# ECG.net
KiCad netlist of a schematic drawn in Altium Designer
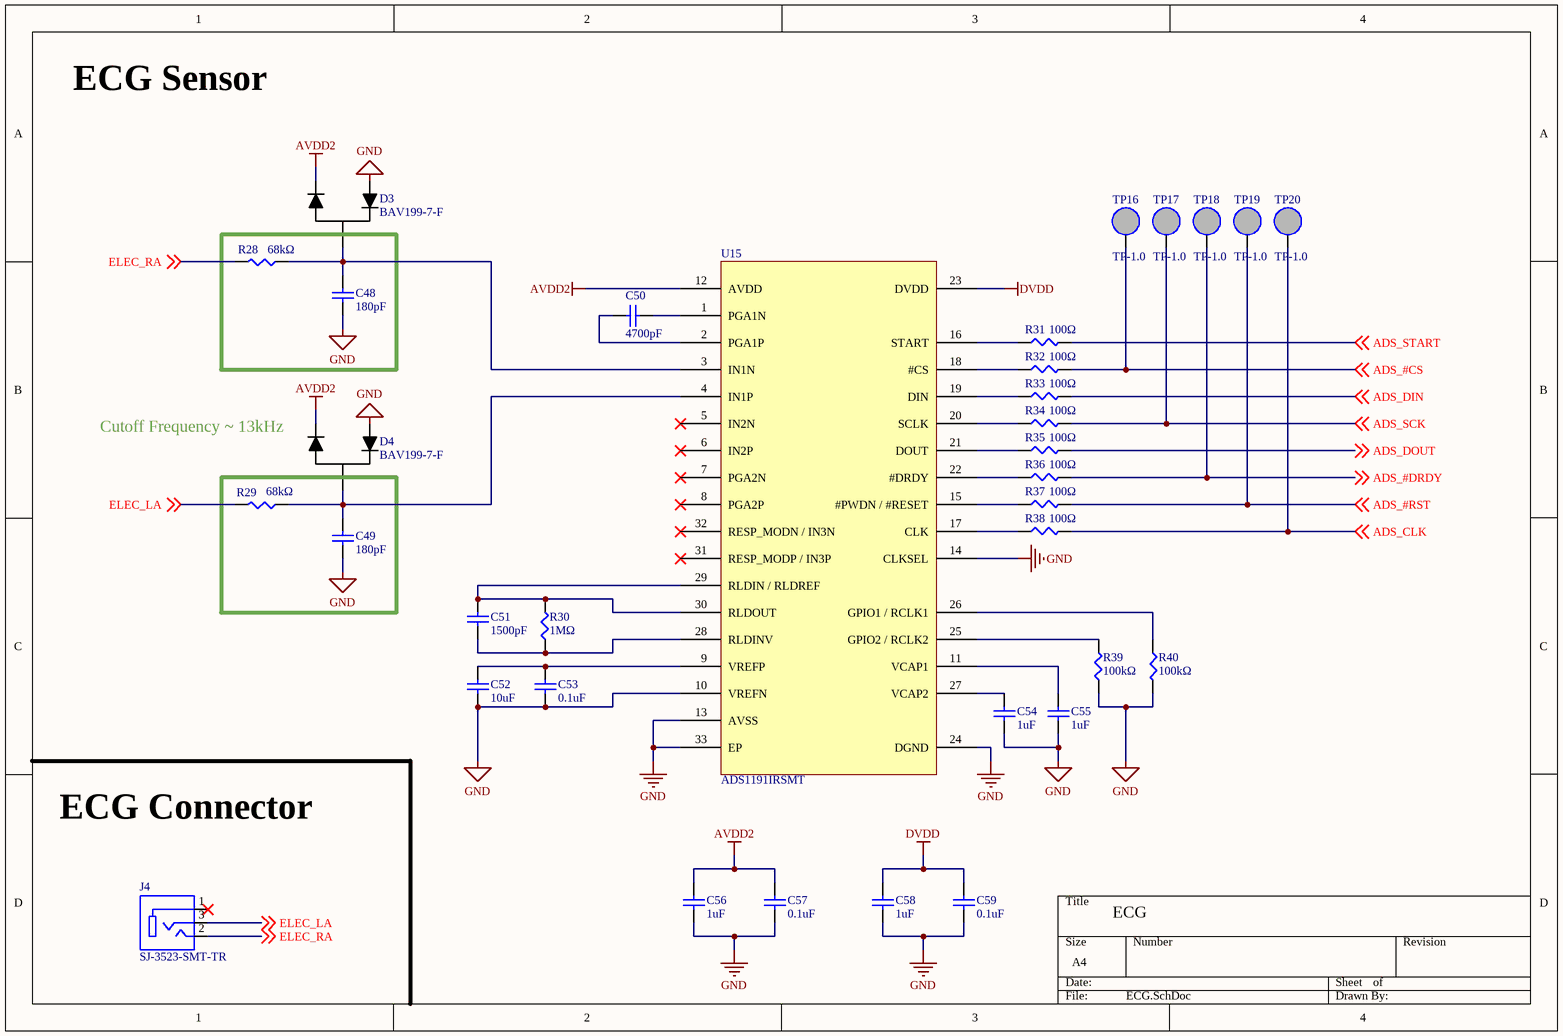
[diagram p0: ECG.SchDoc]

(export (version "E")
  (design (tool "Eeschema 10.0.6"))
  (components
    (comp (ref "C48")
      (value "180pF")
      (footprint "0402")
      (description "MLCC-0402")
      (libsource (lib "MLCC") (part "0402"))
    )
    (comp (ref "C49")
      (value "180pF")
      (footprint "0402")
      (description "MLCC-0402")
      (libsource (lib "MLCC") (part "0402"))
    )
    (comp (ref "C50")
      (value "4700pF")
      (footprint "0402")
      (description "MLCC-0402")
      (libsource (lib "MLCC") (part "0402"))
    )
    (comp (ref "C51")
      (value "1500pF")
      (footprint "0402")
      (description "MLCC-0402")
      (libsource (lib "MLCC") (part "0402"))
    )
    (comp (ref "C52")
      (value "10uF")
      (footprint "0603")
      (description "MLCC-0603")
      (libsource (lib "MLCC") (part "0603"))
    )
    (comp (ref "C53")
      (value "0.1uF")
      (footprint "0402")
      (description "MLCC-0402")
      (libsource (lib "MLCC") (part "0402"))
    )
    (comp (ref "C54")
      (value "1uF")
      (footprint "0402")
      (description "MLCC-0402")
      (libsource (lib "MLCC") (part "0402"))
    )
    (comp (ref "C55")
      (value "1uF")
      (footprint "0402")
      (description "MLCC-0402")
      (libsource (lib "MLCC") (part "0402"))
    )
    (comp (ref "C56")
      (value "1uF")
      (footprint "0402")
      (description "MLCC-0402")
      (libsource (lib "MLCC") (part "0402"))
    )
    (comp (ref "C57")
      (value "0.1uF")
      (footprint "0402")
      (description "MLCC-0402")
      (libsource (lib "MLCC") (part "0402"))
    )
    (comp (ref "C58")
      (value "1uF")
      (footprint "0402")
      (description "MLCC-0402")
      (libsource (lib "MLCC") (part "0402"))
    )
    (comp (ref "C59")
      (value "0.1uF")
      (footprint "0402")
      (description "MLCC-0402")
      (libsource (lib "MLCC") (part "0402"))
    )
    (comp (ref "D3")
      (value "BAV199-7-F")
      (footprint "SOT-23")
      (description "Dual Surface Mount Low Leakage Diode")
      (libsource (lib "BAV199") (part "BAV199-7-F"))
    )
    (comp (ref "D4")
      (value "BAV199-7-F")
      (footprint "SOT-23")
      (description "Dual Surface Mount Low Leakage Diode")
      (libsource (lib "BAV199") (part "BAV199-7-F"))
    )
    (comp (ref "J4")
      (value "SJ-3523-SMT-TR")
      (footprint "CUI_SJ-3523-SMT-TR")
      (description "3.5 mm, Stereo, Right Angle, Surface Mount _SMT_, Audio Jack Connector")
      (fields (field (name "MF") "CUI Devices"))
      (libsource (lib "SJ-3523-SMT-TR") (part "SJ-3523-SMT-TR"))
    )
    (comp (ref "R28")
      (value "68kΩ")
      (footprint "0402")
      (description "Resistor_SMD_0402")
      (fields (field (name "AUTHORBY") "yjlab"))
      (libsource (lib "Resistor") (part "0402"))
    )
    (comp (ref "R29")
      (value "68kΩ")
      (footprint "0402")
      (description "Resistor_SMD_0402")
      (fields (field (name "AUTHORBY") "yjlab"))
      (libsource (lib "Resistor") (part "0402"))
    )
    (comp (ref "R30")
      (value "1MΩ")
      (footprint "0402")
      (description "Resistor_SMD_0402")
      (fields (field (name "AUTHORBY") "yjlab"))
      (libsource (lib "Resistor") (part "0402"))
    )
    (comp (ref "R31")
      (value "100Ω")
      (footprint "0402")
      (description "Resistor_SMD_0402")
      (fields (field (name "AUTHORBY") "yjlab"))
      (libsource (lib "Resistor") (part "0402"))
    )
    (comp (ref "R32")
      (value "100Ω")
      (footprint "0402")
      (description "Resistor_SMD_0402")
      (fields (field (name "AUTHORBY") "yjlab"))
      (libsource (lib "Resistor") (part "0402"))
    )
    (comp (ref "R33")
      (value "100Ω")
      (footprint "0402")
      (description "Resistor_SMD_0402")
      (fields (field (name "AUTHORBY") "yjlab"))
      (libsource (lib "Resistor") (part "0402"))
    )
    (comp (ref "R34")
      (value "100Ω")
      (footprint "0402")
      (description "Resistor_SMD_0402")
      (fields (field (name "AUTHORBY") "yjlab"))
      (libsource (lib "Resistor") (part "0402"))
    )
    (comp (ref "R35")
      (value "100Ω")
      (footprint "0402")
      (description "Resistor_SMD_0402")
      (fields (field (name "AUTHORBY") "yjlab"))
      (libsource (lib "Resistor") (part "0402"))
    )
    (comp (ref "R36")
      (value "100Ω")
      (footprint "0402")
      (description "Resistor_SMD_0402")
      (fields (field (name "AUTHORBY") "yjlab"))
      (libsource (lib "Resistor") (part "0402"))
    )
    (comp (ref "R37")
      (value "100Ω")
      (footprint "0402")
      (description "Resistor_SMD_0402")
      (fields (field (name "AUTHORBY") "yjlab"))
      (libsource (lib "Resistor") (part "0402"))
    )
    (comp (ref "R38")
      (value "100Ω")
      (footprint "0402")
      (description "Resistor_SMD_0402")
      (fields (field (name "AUTHORBY") "yjlab"))
      (libsource (lib "Resistor") (part "0402"))
    )
    (comp (ref "R39")
      (value "100kΩ")
      (footprint "0402")
      (description "Resistor_SMD_0402")
      (fields (field (name "AUTHORBY") "yjlab"))
      (libsource (lib "Resistor") (part "0402"))
    )
    (comp (ref "R40")
      (value "100kΩ")
      (footprint "0402")
      (description "Resistor_SMD_0402")
      (fields (field (name "AUTHORBY") "yjlab"))
      (libsource (lib "Resistor") (part "0402"))
    )
    (comp (ref "TP16")
      (value "TP-1.0")
      (footprint "Testpoint")
      (libsource (lib "Testpoint") (part "Testpoint"))
    )
    (comp (ref "TP17")
      (value "TP-1.0")
      (footprint "Testpoint")
      (libsource (lib "Testpoint") (part "Testpoint"))
    )
    (comp (ref "TP18")
      (value "TP-1.0")
      (footprint "Testpoint")
      (libsource (lib "Testpoint") (part "Testpoint"))
    )
    (comp (ref "TP19")
      (value "TP-1.0")
      (footprint "Testpoint")
      (libsource (lib "Testpoint") (part "Testpoint"))
    )
    (comp (ref "TP20")
      (value "TP-1.0")
      (footprint "Testpoint")
      (libsource (lib "Testpoint") (part "Testpoint"))
    )
    (comp (ref "U15")
      (value "ADS1191IRSMT")
      (footprint "VQFN-32")
      (description "Biopotential Measurement ADC, 2 Channel, 16 Bit")
      (libsource (lib "ADS119x") (part "ADS1191IRSMT"))
    )
  )
  (nets
    (net (code "1") (name "ADS_#CS") (class "Default")
      (node (ref "R32") (pin "2") (pinfunction "2_2") (pintype "passive"))
      (node (ref "TP16") (pin "1") (pinfunction "1_1") (pintype "passive"))
    )
    (net (code "2") (name "ADS_#DRDY") (class "Default")
      (node (ref "R36") (pin "2") (pinfunction "2_2") (pintype "passive"))
      (node (ref "TP18") (pin "1") (pinfunction "1_1") (pintype "passive"))
    )
    (net (code "3") (name "ADS_#RST") (class "Default")
      (node (ref "R37") (pin "2") (pinfunction "2_2") (pintype "passive"))
      (node (ref "TP19") (pin "1") (pinfunction "1_1") (pintype "passive"))
    )
    (net (code "4") (name "ADS_CLK") (class "Default")
      (node (ref "R38") (pin "2") (pinfunction "2_2") (pintype "passive"))
      (node (ref "TP20") (pin "1") (pinfunction "1_1") (pintype "passive"))
    )
    (net (code "5") (name "ADS_DIN") (class "Default")
      (node (ref "R33") (pin "2") (pinfunction "2_2") (pintype "passive"))
    )
    (net (code "6") (name "ADS_DOUT") (class "Default")
      (node (ref "R35") (pin "2") (pinfunction "2_2") (pintype "passive"))
    )
    (net (code "7") (name "ADS_SCK") (class "Default")
      (node (ref "R34") (pin "2") (pinfunction "2_2") (pintype "passive"))
      (node (ref "TP17") (pin "1") (pinfunction "1_1") (pintype "passive"))
    )
    (net (code "8") (name "ADS_START") (class "Default")
      (node (ref "R31") (pin "2") (pinfunction "2_2") (pintype "passive"))
    )
    (net (code "9") (name "AVDD2") (class "Default")
      (node (ref "C56") (pin "2") (pinfunction "2_2") (pintype "passive"))
      (node (ref "C57") (pin "2") (pinfunction "2_2") (pintype "passive"))
      (node (ref "D3") (pin "3") (pinfunction "Cathode_3") (pintype "passive"))
      (node (ref "D4") (pin "3") (pinfunction "Cathode_3") (pintype "passive"))
      (node (ref "U15") (pin "12") (pinfunction "AVDD_12") (pintype "passive"))
    )
    (net (code "10") (name "DVDD") (class "Default")
      (node (ref "C58") (pin "2") (pinfunction "2_2") (pintype "passive"))
      (node (ref "C59") (pin "2") (pinfunction "2_2") (pintype "passive"))
      (node (ref "U15") (pin "23") (pinfunction "DVDD_23") (pintype "passive"))
    )
    (net (code "11") (name "ELEC_LA") (class "Default")
      (node (ref "J4") (pin "3") (pinfunction "3_3") (pintype "passive"))
      (node (ref "R29") (pin "2") (pinfunction "2_2") (pintype "passive"))
    )
    (net (code "12") (name "ELEC_RA") (class "Default")
      (node (ref "J4") (pin "2") (pinfunction "2_2") (pintype "passive"))
      (node (ref "R28") (pin "2") (pinfunction "2_2") (pintype "passive"))
    )
    (net (code "13") (name "GND") (class "Default")
      (node (ref "C48") (pin "1") (pinfunction "1_1") (pintype "passive"))
      (node (ref "C49") (pin "1") (pinfunction "1_1") (pintype "passive"))
      (node (ref "C52") (pin "1") (pinfunction "1_1") (pintype "passive"))
      (node (ref "C53") (pin "1") (pinfunction "1_1") (pintype "passive"))
      (node (ref "C54") (pin "2") (pinfunction "2_2") (pintype "passive"))
      (node (ref "C55") (pin "2") (pinfunction "2_2") (pintype "passive"))
      (node (ref "C56") (pin "1") (pinfunction "1_1") (pintype "passive"))
      (node (ref "C57") (pin "1") (pinfunction "1_1") (pintype "passive"))
      (node (ref "C58") (pin "1") (pinfunction "1_1") (pintype "passive"))
      (node (ref "C59") (pin "1") (pinfunction "1_1") (pintype "passive"))
      (node (ref "D3") (pin "2") (pinfunction "Anode_2") (pintype "passive"))
      (node (ref "D4") (pin "2") (pinfunction "Anode_2") (pintype "passive"))
      (node (ref "R39") (pin "1") (pinfunction "1_1") (pintype "passive"))
      (node (ref "R40") (pin "2") (pinfunction "2_2") (pintype "passive"))
      (node (ref "U15") (pin "10") (pinfunction "VREFN_10") (pintype "passive"))
      (node (ref "U15") (pin "13") (pinfunction "AVSS_13") (pintype "passive"))
      (node (ref "U15") (pin "14") (pinfunction "CLKSEL_14") (pintype "passive"))
      (node (ref "U15") (pin "24") (pinfunction "DGND_24") (pintype "passive"))
      (node (ref "U15") (pin "33") (pinfunction "EP_33") (pintype "passive"))
    )
    (net (code "14") (name "Net-(D3-Common)") (class "Default")
      (node (ref "C48") (pin "2") (pinfunction "2_2") (pintype "passive"))
      (node (ref "D3") (pin "1") (pinfunction "Common_1") (pintype "passive"))
      (node (ref "R28") (pin "1") (pinfunction "1_1") (pintype "passive"))
      (node (ref "U15") (pin "3") (pinfunction "IN1N_3") (pintype "passive"))
    )
    (net (code "15") (name "Net-(D4-Common)") (class "Default")
      (node (ref "C49") (pin "2") (pinfunction "2_2") (pintype "passive"))
      (node (ref "D4") (pin "1") (pinfunction "Common_1") (pintype "passive"))
      (node (ref "R29") (pin "1") (pinfunction "1_1") (pintype "passive"))
      (node (ref "U15") (pin "4") (pinfunction "IN1P_4") (pintype "passive"))
    )
    (net (code "16") (name "Net-(U15-#CS)") (class "Default")
      (node (ref "R32") (pin "1") (pinfunction "1_1") (pintype "passive"))
      (node (ref "U15") (pin "18") (pinfunction "#CS_18") (pintype "passive"))
    )
    (net (code "17") (name "Net-(U15-#DRDY)") (class "Default")
      (node (ref "R36") (pin "1") (pinfunction "1_1") (pintype "passive"))
      (node (ref "U15") (pin "22") (pinfunction "#DRDY_22") (pintype "passive"))
    )
    (net (code "18") (name "Net-(U15-#PWDN_{slash}_#RESET)") (class "Default")
      (node (ref "R37") (pin "1") (pinfunction "1_1") (pintype "passive"))
      (node (ref "U15") (pin "15") (pinfunction "#PWDN_/_#RESET_15") (pintype "passive"))
    )
    (net (code "19") (name "Net-(U15-CLK)") (class "Default")
      (node (ref "R38") (pin "1") (pinfunction "1_1") (pintype "passive"))
      (node (ref "U15") (pin "17") (pinfunction "CLK_17") (pintype "passive"))
    )
    (net (code "20") (name "Net-(U15-DIN)") (class "Default")
      (node (ref "R33") (pin "1") (pinfunction "1_1") (pintype "passive"))
      (node (ref "U15") (pin "19") (pinfunction "DIN_19") (pintype "passive"))
    )
    (net (code "21") (name "Net-(U15-DOUT)") (class "Default")
      (node (ref "R35") (pin "1") (pinfunction "1_1") (pintype "passive"))
      (node (ref "U15") (pin "21") (pinfunction "DOUT_21") (pintype "passive"))
    )
    (net (code "22") (name "Net-(U15-GPIO1_{slash}_RCLK1)") (class "Default")
      (node (ref "R40") (pin "1") (pinfunction "1_1") (pintype "passive"))
      (node (ref "U15") (pin "26") (pinfunction "GPIO1_/_RCLK1_26") (pintype "passive"))
    )
    (net (code "23") (name "Net-(U15-GPIO2_{slash}_RCLK2)") (class "Default")
      (node (ref "R39") (pin "2") (pinfunction "2_2") (pintype "passive"))
      (node (ref "U15") (pin "25") (pinfunction "GPIO2_/_RCLK2_25") (pintype "passive"))
    )
    (net (code "24") (name "Net-(U15-PGA1N)") (class "Default")
      (node (ref "C50") (pin "2") (pinfunction "2_2") (pintype "passive"))
      (node (ref "U15") (pin "1") (pinfunction "PGA1N_1") (pintype "passive"))
    )
    (net (code "25") (name "Net-(U15-PGA1P)") (class "Default")
      (node (ref "C50") (pin "1") (pinfunction "1_1") (pintype "passive"))
      (node (ref "U15") (pin "2") (pinfunction "PGA1P_2") (pintype "passive"))
    )
    (net (code "26") (name "Net-(U15-RLDINV)") (class "Default")
      (node (ref "C51") (pin "1") (pinfunction "1_1") (pintype "passive"))
      (node (ref "R30") (pin "1") (pinfunction "1_1") (pintype "passive"))
      (node (ref "U15") (pin "28") (pinfunction "RLDINV_28") (pintype "passive"))
    )
    (net (code "27") (name "Net-(U15-RLDIN_{slash}_RLDREF)") (class "Default")
      (node (ref "C51") (pin "2") (pinfunction "2_2") (pintype "passive"))
      (node (ref "R30") (pin "2") (pinfunction "2_2") (pintype "passive"))
      (node (ref "U15") (pin "29") (pinfunction "RLDIN_/_RLDREF_29") (pintype "passive"))
      (node (ref "U15") (pin "30") (pinfunction "RLDOUT_30") (pintype "passive"))
    )
    (net (code "28") (name "Net-(U15-SCLK)") (class "Default")
      (node (ref "R34") (pin "1") (pinfunction "1_1") (pintype "passive"))
      (node (ref "U15") (pin "20") (pinfunction "SCLK_20") (pintype "passive"))
    )
    (net (code "29") (name "Net-(U15-START)") (class "Default")
      (node (ref "R31") (pin "1") (pinfunction "1_1") (pintype "passive"))
      (node (ref "U15") (pin "16") (pinfunction "START_16") (pintype "passive"))
    )
    (net (code "30") (name "Net-(U15-VCAP1)") (class "Default")
      (node (ref "C55") (pin "1") (pinfunction "1_1") (pintype "passive"))
      (node (ref "U15") (pin "11") (pinfunction "VCAP1_11") (pintype "passive"))
    )
    (net (code "31") (name "Net-(U15-VCAP2)") (class "Default")
      (node (ref "C54") (pin "1") (pinfunction "1_1") (pintype "passive"))
      (node (ref "U15") (pin "27") (pinfunction "VCAP2_27") (pintype "passive"))
    )
    (net (code "32") (name "Net-(U15-VREFP)") (class "Default")
      (node (ref "C52") (pin "2") (pinfunction "2_2") (pintype "passive"))
      (node (ref "C53") (pin "2") (pinfunction "2_2") (pintype "passive"))
      (node (ref "U15") (pin "9") (pinfunction "VREFP_9") (pintype "passive"))
    )
    (net (code "33") (name "unconnected-(J4-Pad1)") (class "Default")
      (node (ref "J4") (pin "1") (pinfunction "1_1") (pintype "passive+no_connect"))
    )
    (net (code "34") (name "unconnected-(U15-IN2N-Pad5)") (class "Default")
      (node (ref "U15") (pin "5") (pinfunction "IN2N_5") (pintype "passive+no_connect"))
    )
    (net (code "35") (name "unconnected-(U15-IN2P-Pad6)") (class "Default")
      (node (ref "U15") (pin "6") (pinfunction "IN2P_6") (pintype "passive+no_connect"))
    )
    (net (code "36") (name "unconnected-(U15-PGA2N-Pad7)") (class "Default")
      (node (ref "U15") (pin "7") (pinfunction "PGA2N_7") (pintype "passive+no_connect"))
    )
    (net (code "37") (name "unconnected-(U15-PGA2P-Pad8)") (class "Default")
      (node (ref "U15") (pin "8") (pinfunction "PGA2P_8") (pintype "passive+no_connect"))
    )
    (net (code "38") (name "unconnected-(U15-RESP_MODN_{slash}_IN3N-Pad32)") (class "Default")
      (node (ref "U15") (pin "32") (pinfunction "RESP_MODN_/_IN3N_32") (pintype "passive+no_connect"))
    )
    (net (code "39") (name "unconnected-(U15-RESP_MODP_{slash}_IN3P-Pad31)") (class "Default")
      (node (ref "U15") (pin "31") (pinfunction "RESP_MODP_/_IN3P_31") (pintype "passive+no_connect"))
    )
  )
)
